# INR.net
KiCad netlist of a schematic drawn in Altium Designer
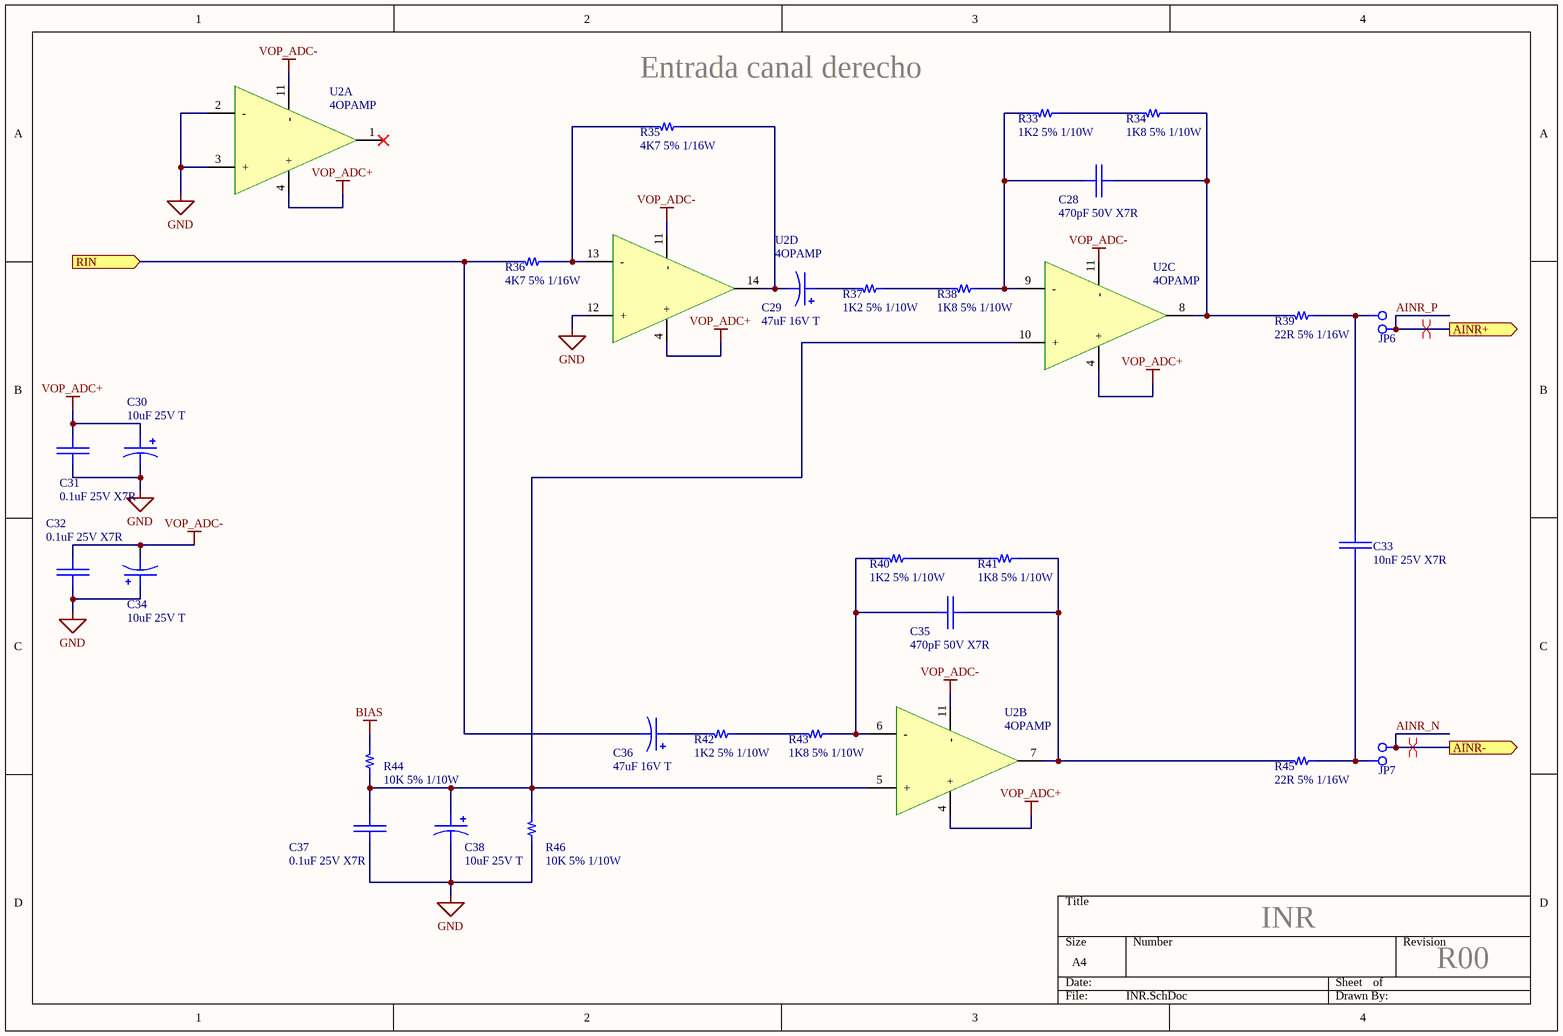
[diagram p0: INR.SchDoc]

(export (version "E")
  (design (tool "Eeschema 10.0.6"))
  (components
    (comp (ref "C28")
      (value "470pF 50V X7R")
      (footprint "C_0805")
      (description "Capacitor de placas paralelas")
      (libsource (lib "Radios_Comunitarias") (part "Capacitor"))
    )
    (comp (ref "C29")
      (value "47uF 16V T")
      (footprint "TANT")
      (description "Capacitor polarizado")
      (libsource (lib "") (part "CapaPol_1"))
    )
    (comp (ref "C30")
      (value "10uF 25V T")
      (footprint "TANT")
      (description "Capacitor polarizado")
      (libsource (lib "Radios_Comunitarias") (part "CapaPol"))
    )
    (comp (ref "C31")
      (value "0.1uF 25V X7R")
      (footprint "C_0805")
      (description "Capacitor de placas paralelas")
      (libsource (lib "Radios_Comunitarias") (part "Capacitor"))
    )
    (comp (ref "C32")
      (value "0.1uF 25V X7R")
      (footprint "C_0805")
      (description "Capacitor de placas paralelas")
      (libsource (lib "Radios_Comunitarias") (part "Capacitor"))
    )
    (comp (ref "C33")
      (value "10nF 25V X7R")
      (footprint "C_0805")
      (description "Capacitor de placas paralelas")
      (libsource (lib "Radios_Comunitarias") (part "Capacitor"))
    )
    (comp (ref "C34")
      (value "10uF 25V T")
      (footprint "TANT")
      (description "Capacitor polarizado")
      (libsource (lib "Radios_Comunitarias") (part "CapaPol"))
    )
    (comp (ref "C35")
      (value "470pF 50V X7R")
      (footprint "C_0805")
      (description "Capacitor de placas paralelas")
      (libsource (lib "Radios_Comunitarias") (part "Capacitor"))
    )
    (comp (ref "C36")
      (value "47uF 16V T")
      (footprint "TANT")
      (description "Capacitor polarizado")
      (libsource (lib "") (part "CapaPol_1"))
    )
    (comp (ref "C37")
      (value "0.1uF 25V X7R")
      (footprint "C_0805")
      (description "Capacitor de placas paralelas")
      (libsource (lib "Radios_Comunitarias") (part "Capacitor"))
    )
    (comp (ref "C38")
      (value "10uF 25V T")
      (footprint "TANT")
      (description "Capacitor polarizado")
      (libsource (lib "Radios_Comunitarias") (part "CapaPol"))
    )
    (comp (ref "JP6")
      (value "Jumper 2x1")
      (footprint "Conn_2_1")
      (libsource (lib "Radios_Comunitarias") (part "Jumper 2x1"))
    )
    (comp (ref "JP7")
      (value "Jumper 2x1")
      (footprint "Conn_2_1")
      (libsource (lib "Radios_Comunitarias") (part "Jumper 2x1"))
    )
    (comp (ref "R33")
      (value "1K2 5% 1/10W")
      (footprint "R_0805")
      (description "Resistencia")
      (libsource (lib "Radios_Comunitarias") (part "Resistor"))
    )
    (comp (ref "R34")
      (value "1K8 5% 1/10W")
      (footprint "R_0805")
      (description "Resistencia")
      (libsource (lib "Radios_Comunitarias") (part "Resistor"))
    )
    (comp (ref "R35")
      (value "4K7 5% 1/16W")
      (footprint "R_0805")
      (description "Resistencia")
      (libsource (lib "Radios_Comunitarias") (part "Resistor"))
    )
    (comp (ref "R36")
      (value "4K7 5% 1/16W")
      (footprint "R_0805")
      (description "Resistencia")
      (libsource (lib "Radios_Comunitarias") (part "Resistor"))
    )
    (comp (ref "R37")
      (value "1K2 5% 1/10W")
      (footprint "R_0805")
      (description "Resistencia")
      (libsource (lib "Radios_Comunitarias") (part "Resistor"))
    )
    (comp (ref "R38")
      (value "1K8 5% 1/10W")
      (footprint "R_0805")
      (description "Resistencia")
      (libsource (lib "Radios_Comunitarias") (part "Resistor"))
    )
    (comp (ref "R39")
      (value "22R 5% 1/16W")
      (footprint "R_0805")
      (description "Resistencia")
      (libsource (lib "Radios_Comunitarias") (part "Resistor"))
    )
    (comp (ref "R40")
      (value "1K2 5% 1/10W")
      (footprint "R_0805")
      (description "Resistencia")
      (libsource (lib "Radios_Comunitarias") (part "Resistor"))
    )
    (comp (ref "R41")
      (value "1K8 5% 1/10W")
      (footprint "R_0805")
      (description "Resistencia")
      (libsource (lib "Radios_Comunitarias") (part "Resistor"))
    )
    (comp (ref "R42")
      (value "1K2 5% 1/10W")
      (footprint "R_0805")
      (description "Resistencia")
      (libsource (lib "Radios_Comunitarias") (part "Resistor"))
    )
    (comp (ref "R43")
      (value "1K8 5% 1/10W")
      (footprint "R_0805")
      (description "Resistencia")
      (libsource (lib "Radios_Comunitarias") (part "Resistor"))
    )
    (comp (ref "R44")
      (value "10K 5% 1/10W")
      (footprint "R_0805")
      (description "Resistencia")
      (libsource (lib "Radios_Comunitarias") (part "Resistor"))
    )
    (comp (ref "R45")
      (value "22R 5% 1/16W")
      (footprint "R_0805")
      (description "Resistencia")
      (libsource (lib "Radios_Comunitarias") (part "Resistor"))
    )
    (comp (ref "R46")
      (value "10K 5% 1/10W")
      (footprint "R_0805")
      (description "Resistencia")
      (libsource (lib "Radios_Comunitarias") (part "Resistor"))
    )
    (comp (ref "U2")
      (value "4OPAMP")
      (footprint "SOIC14")
      (description "Integrado con 4 operacionales")
      (libsource (lib "Radios_Comunitarias") (part "4OPAMP"))
    )
  )
  (nets
    (net (code "1") (name "/AINR_N") (class "Default")
      (node (ref "JP7") (pin "1") (pinfunction "1_1") (pintype "passive"))
    )
    (net (code "2") (name "/AINR_P") (class "Default")
      (node (ref "JP6") (pin "2") (pinfunction "2_2") (pintype "passive"))
    )
    (net (code "3") (name "/RIN") (class "Default")
      (node (ref "C36") (pin "2") (pinfunction "2_2") (pintype "passive"))
      (node (ref "R36") (pin "2") (pinfunction "2_2") (pintype "passive"))
    )
    (net (code "4") (name "BIAS") (class "Default")
      (node (ref "R44") (pin "2") (pinfunction "2_2") (pintype "passive"))
    )
    (net (code "5") (name "GND") (class "Default")
      (node (ref "C30") (pin "2") (pinfunction "2_2") (pintype "passive"))
      (node (ref "C31") (pin "2") (pinfunction "2_2") (pintype "passive"))
      (node (ref "C32") (pin "2") (pinfunction "2_2") (pintype "passive"))
      (node (ref "C34") (pin "1") (pinfunction "1_1") (pintype "passive"))
      (node (ref "C37") (pin "2") (pinfunction "2_2") (pintype "passive"))
      (node (ref "C38") (pin "2") (pinfunction "2_2") (pintype "passive"))
      (node (ref "R46") (pin "1") (pinfunction "1_1") (pintype "passive"))
      (node (ref "U2") (pin "12") (pinfunction "+_12") (pintype "passive"))
      (node (ref "U2") (pin "2") (pinfunction "-_2") (pintype "passive"))
      (node (ref "U2") (pin "3") (pinfunction "+_3") (pintype "passive"))
    )
    (net (code "6") (name "Net-(C28-Pad1)") (class "Default")
      (node (ref "C28") (pin "1") (pinfunction "1_1") (pintype "passive"))
      (node (ref "R33") (pin "2") (pinfunction "2_2") (pintype "passive"))
      (node (ref "R38") (pin "1") (pinfunction "1_1") (pintype "passive"))
      (node (ref "U2") (pin "9") (pinfunction "-_9") (pintype "passive"))
    )
    (net (code "7") (name "Net-(C29-Pad1)") (class "Default")
      (node (ref "C29") (pin "1") (pinfunction "1_1") (pintype "passive"))
      (node (ref "R37") (pin "2") (pinfunction "2_2") (pintype "passive"))
    )
    (net (code "8") (name "Net-(C33-Pad1)") (class "Default")
      (node (ref "C33") (pin "1") (pinfunction "1_1") (pintype "passive"))
      (node (ref "JP7") (pin "2") (pinfunction "2_2") (pintype "passive"))
      (node (ref "R45") (pin "1") (pinfunction "1_1") (pintype "passive"))
    )
    (net (code "9") (name "Net-(C33-Pad2)") (class "Default")
      (node (ref "C33") (pin "2") (pinfunction "2_2") (pintype "passive"))
      (node (ref "JP6") (pin "1") (pinfunction "1_1") (pintype "passive"))
      (node (ref "R39") (pin "1") (pinfunction "1_1") (pintype "passive"))
    )
    (net (code "10") (name "Net-(C35-Pad1)") (class "Default")
      (node (ref "C35") (pin "1") (pinfunction "1_1") (pintype "passive"))
      (node (ref "R40") (pin "2") (pinfunction "2_2") (pintype "passive"))
      (node (ref "R43") (pin "1") (pinfunction "1_1") (pintype "passive"))
      (node (ref "U2") (pin "6") (pinfunction "-_6") (pintype "passive"))
    )
    (net (code "11") (name "Net-(C36-Pad1)") (class "Default")
      (node (ref "C36") (pin "1") (pinfunction "1_1") (pintype "passive"))
      (node (ref "R42") (pin "2") (pinfunction "2_2") (pintype "passive"))
    )
    (net (code "12") (name "Net-(C37-Pad1)") (class "Default")
      (node (ref "C37") (pin "1") (pinfunction "1_1") (pintype "passive"))
      (node (ref "C38") (pin "1") (pinfunction "1_1") (pintype "passive"))
      (node (ref "R44") (pin "1") (pinfunction "1_1") (pintype "passive"))
      (node (ref "R46") (pin "2") (pinfunction "2_2") (pintype "passive"))
      (node (ref "U2") (pin "10") (pinfunction "+_10") (pintype "passive"))
      (node (ref "U2") (pin "5") (pinfunction "+_5") (pintype "passive"))
    )
    (net (code "13") (name "Net-(R33-Pad1)") (class "Default")
      (node (ref "R33") (pin "1") (pinfunction "1_1") (pintype "passive"))
      (node (ref "R34") (pin "2") (pinfunction "2_2") (pintype "passive"))
    )
    (net (code "14") (name "Net-(R35-Pad2)") (class "Default")
      (node (ref "R35") (pin "2") (pinfunction "2_2") (pintype "passive"))
      (node (ref "R36") (pin "1") (pinfunction "1_1") (pintype "passive"))
      (node (ref "U2") (pin "13") (pinfunction "-_13") (pintype "passive"))
    )
    (net (code "15") (name "Net-(R37-Pad1)") (class "Default")
      (node (ref "R37") (pin "1") (pinfunction "1_1") (pintype "passive"))
      (node (ref "R38") (pin "2") (pinfunction "2_2") (pintype "passive"))
    )
    (net (code "16") (name "Net-(R40-Pad1)") (class "Default")
      (node (ref "R40") (pin "1") (pinfunction "1_1") (pintype "passive"))
      (node (ref "R41") (pin "2") (pinfunction "2_2") (pintype "passive"))
    )
    (net (code "17") (name "Net-(R42-Pad1)") (class "Default")
      (node (ref "R42") (pin "1") (pinfunction "1_1") (pintype "passive"))
      (node (ref "R43") (pin "2") (pinfunction "2_2") (pintype "passive"))
    )
    (net (code "18") (name "Net-(U2B-OUT)") (class "Default")
      (node (ref "C35") (pin "2") (pinfunction "2_2") (pintype "passive"))
      (node (ref "R41") (pin "1") (pinfunction "1_1") (pintype "passive"))
      (node (ref "R45") (pin "2") (pinfunction "2_2") (pintype "passive"))
      (node (ref "U2") (pin "7") (pinfunction "OUT_7") (pintype "passive"))
    )
    (net (code "19") (name "Net-(U2C-OUT)") (class "Default")
      (node (ref "C28") (pin "2") (pinfunction "2_2") (pintype "passive"))
      (node (ref "R34") (pin "1") (pinfunction "1_1") (pintype "passive"))
      (node (ref "R39") (pin "2") (pinfunction "2_2") (pintype "passive"))
      (node (ref "U2") (pin "8") (pinfunction "OUT_8") (pintype "passive"))
    )
    (net (code "20") (name "Net-(U2D-OUT)") (class "Default")
      (node (ref "C29") (pin "2") (pinfunction "2_2") (pintype "passive"))
      (node (ref "R35") (pin "1") (pinfunction "1_1") (pintype "passive"))
      (node (ref "U2") (pin "14") (pinfunction "OUT_14") (pintype "passive"))
    )
    (net (code "21") (name "VOP_ADC+") (class "Default")
      (node (ref "C30") (pin "1") (pinfunction "1_1") (pintype "passive"))
      (node (ref "C31") (pin "1") (pinfunction "1_1") (pintype "passive"))
      (node (ref "U2") (pin "4") (pinfunction "+_4") (pintype "power_in"))
    )
    (net (code "22") (name "VOP_ADC-") (class "Default")
      (node (ref "C32") (pin "1") (pinfunction "1_1") (pintype "passive"))
      (node (ref "C34") (pin "2") (pinfunction "2_2") (pintype "passive"))
      (node (ref "U2") (pin "11") (pinfunction "-_11") (pintype "passive"))
    )
    (net (code "23") (name "unconnected-(U2A-OUT-Pad1)") (class "Default")
      (node (ref "U2") (pin "1") (pinfunction "OUT_1") (pintype "passive+no_connect"))
    )
  )
)
